# LEDS.net
KiCad netlist of a schematic drawn in Altium Designer
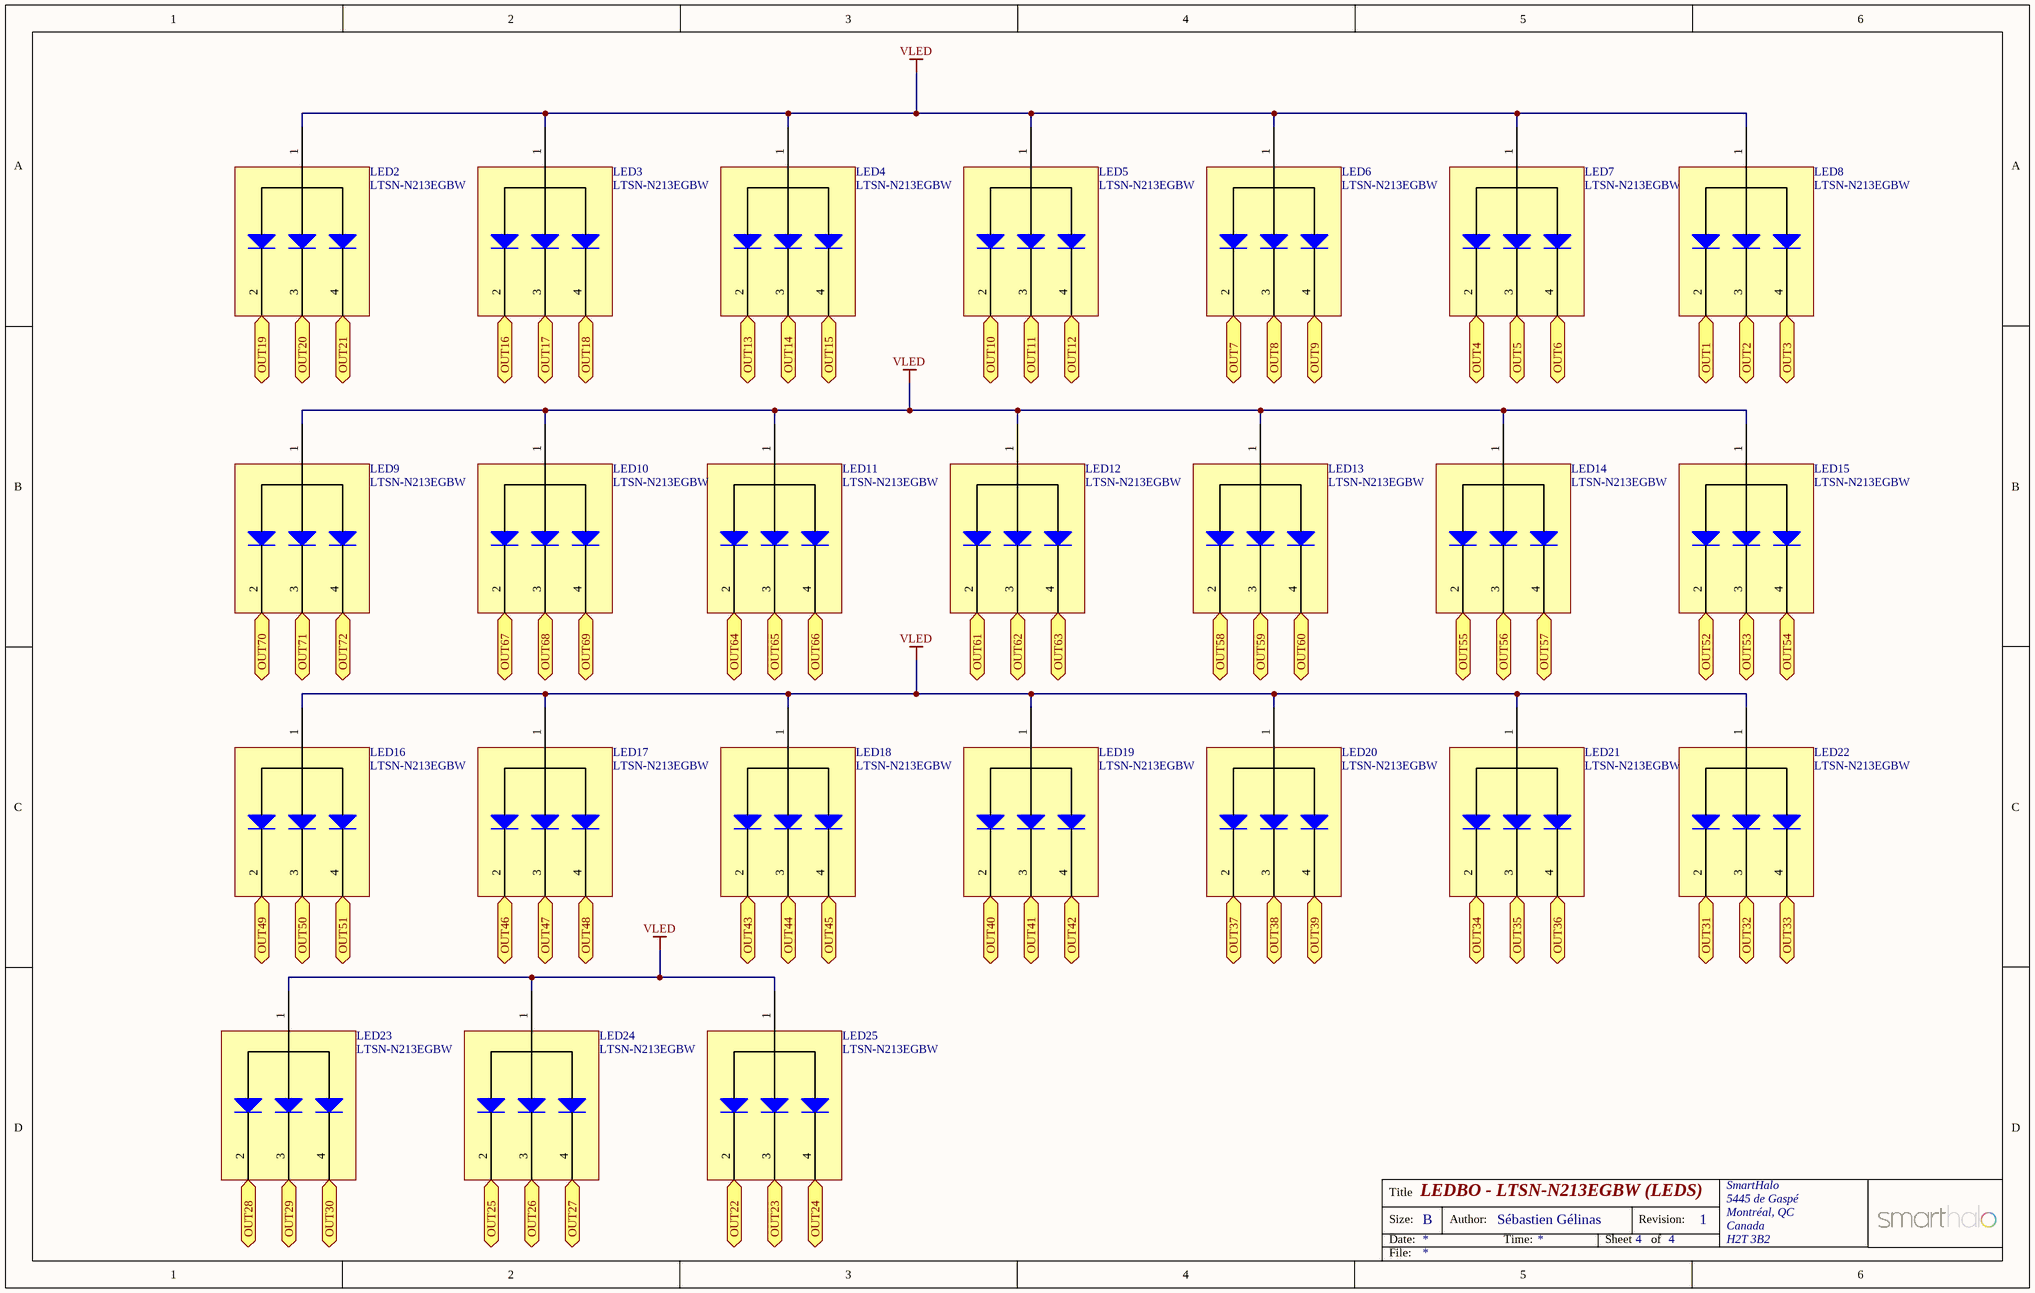
[diagram p0: LEDS.SchDoc]

(export (version "E")
  (design (tool "Eeschema 10.0.6"))
  (components
    (comp (ref "LED2")
      (value "LTSN-N213EGBW")
      (footprint "LTSN-N213EGBW")
      (description "LED SMD LTSN-N213EGBW")
      (fields (field (name "MANUFACTURER") "LiteOn"))
      (libsource (lib "SmartHalo") (part "LTSN-N213EGBW"))
    )
    (comp (ref "LED3")
      (value "LTSN-N213EGBW")
      (footprint "LTSN-N213EGBW")
      (description "LED SMD LTSN-N213EGBW")
      (fields (field (name "MANUFACTURER") "LiteOn"))
      (libsource (lib "SmartHalo") (part "LTSN-N213EGBW"))
    )
    (comp (ref "LED4")
      (value "LTSN-N213EGBW")
      (footprint "LTSN-N213EGBW")
      (description "LED SMD LTSN-N213EGBW")
      (fields (field (name "MANUFACTURER") "LiteOn"))
      (libsource (lib "SmartHalo") (part "LTSN-N213EGBW"))
    )
    (comp (ref "LED5")
      (value "LTSN-N213EGBW")
      (footprint "LTSN-N213EGBW")
      (description "LED SMD LTSN-N213EGBW")
      (fields (field (name "MANUFACTURER") "LiteOn"))
      (libsource (lib "SmartHalo") (part "LTSN-N213EGBW"))
    )
    (comp (ref "LED6")
      (value "LTSN-N213EGBW")
      (footprint "LTSN-N213EGBW")
      (description "LED SMD LTSN-N213EGBW")
      (fields (field (name "MANUFACTURER") "LiteOn"))
      (libsource (lib "SmartHalo") (part "LTSN-N213EGBW"))
    )
    (comp (ref "LED7")
      (value "LTSN-N213EGBW")
      (footprint "LTSN-N213EGBW")
      (description "LED SMD LTSN-N213EGBW")
      (fields (field (name "MANUFACTURER") "LiteOn"))
      (libsource (lib "SmartHalo") (part "LTSN-N213EGBW"))
    )
    (comp (ref "LED8")
      (value "LTSN-N213EGBW")
      (footprint "LTSN-N213EGBW")
      (description "LED SMD LTSN-N213EGBW")
      (fields (field (name "MANUFACTURER") "LiteOn"))
      (libsource (lib "SmartHalo") (part "LTSN-N213EGBW"))
    )
    (comp (ref "LED9")
      (value "LTSN-N213EGBW")
      (footprint "LTSN-N213EGBW")
      (description "LED SMD LTSN-N213EGBW")
      (fields (field (name "MANUFACTURER") "LiteOn"))
      (libsource (lib "SmartHalo") (part "LTSN-N213EGBW"))
    )
    (comp (ref "LED10")
      (value "LTSN-N213EGBW")
      (footprint "LTSN-N213EGBW")
      (description "LED SMD LTSN-N213EGBW")
      (fields (field (name "MANUFACTURER") "LiteOn"))
      (libsource (lib "SmartHalo") (part "LTSN-N213EGBW"))
    )
    (comp (ref "LED11")
      (value "LTSN-N213EGBW")
      (footprint "LTSN-N213EGBW")
      (description "LED SMD LTSN-N213EGBW")
      (fields (field (name "MANUFACTURER") "LiteOn"))
      (libsource (lib "SmartHalo") (part "LTSN-N213EGBW"))
    )
    (comp (ref "LED12")
      (value "LTSN-N213EGBW")
      (footprint "LTSN-N213EGBW")
      (description "LED SMD LTSN-N213EGBW")
      (fields (field (name "MANUFACTURER") "LiteOn"))
      (libsource (lib "SmartHalo") (part "LTSN-N213EGBW"))
    )
    (comp (ref "LED13")
      (value "LTSN-N213EGBW")
      (footprint "LTSN-N213EGBW")
      (description "LED SMD LTSN-N213EGBW")
      (fields (field (name "MANUFACTURER") "LiteOn"))
      (libsource (lib "SmartHalo") (part "LTSN-N213EGBW"))
    )
    (comp (ref "LED14")
      (value "LTSN-N213EGBW")
      (footprint "LTSN-N213EGBW")
      (description "LED SMD LTSN-N213EGBW")
      (fields (field (name "MANUFACTURER") "LiteOn"))
      (libsource (lib "SmartHalo") (part "LTSN-N213EGBW"))
    )
    (comp (ref "LED15")
      (value "LTSN-N213EGBW")
      (footprint "LTSN-N213EGBW")
      (description "LED SMD LTSN-N213EGBW")
      (fields (field (name "MANUFACTURER") "LiteOn"))
      (libsource (lib "SmartHalo") (part "LTSN-N213EGBW"))
    )
    (comp (ref "LED16")
      (value "LTSN-N213EGBW")
      (footprint "LTSN-N213EGBW")
      (description "LED SMD LTSN-N213EGBW")
      (fields (field (name "MANUFACTURER") "LiteOn"))
      (libsource (lib "SmartHalo") (part "LTSN-N213EGBW"))
    )
    (comp (ref "LED17")
      (value "LTSN-N213EGBW")
      (footprint "LTSN-N213EGBW")
      (description "LED SMD LTSN-N213EGBW")
      (fields (field (name "MANUFACTURER") "LiteOn"))
      (libsource (lib "SmartHalo") (part "LTSN-N213EGBW"))
    )
    (comp (ref "LED18")
      (value "LTSN-N213EGBW")
      (footprint "LTSN-N213EGBW")
      (description "LED SMD LTSN-N213EGBW")
      (fields (field (name "MANUFACTURER") "LiteOn"))
      (libsource (lib "SmartHalo") (part "LTSN-N213EGBW"))
    )
    (comp (ref "LED19")
      (value "LTSN-N213EGBW")
      (footprint "LTSN-N213EGBW")
      (description "LED SMD LTSN-N213EGBW")
      (fields (field (name "MANUFACTURER") "LiteOn"))
      (libsource (lib "SmartHalo") (part "LTSN-N213EGBW"))
    )
    (comp (ref "LED20")
      (value "LTSN-N213EGBW")
      (footprint "LTSN-N213EGBW")
      (description "LED SMD LTSN-N213EGBW")
      (fields (field (name "MANUFACTURER") "LiteOn"))
      (libsource (lib "SmartHalo") (part "LTSN-N213EGBW"))
    )
    (comp (ref "LED21")
      (value "LTSN-N213EGBW")
      (footprint "LTSN-N213EGBW")
      (description "LED SMD LTSN-N213EGBW")
      (fields (field (name "MANUFACTURER") "LiteOn"))
      (libsource (lib "SmartHalo") (part "LTSN-N213EGBW"))
    )
    (comp (ref "LED22")
      (value "LTSN-N213EGBW")
      (footprint "LTSN-N213EGBW")
      (description "LED SMD LTSN-N213EGBW")
      (fields (field (name "MANUFACTURER") "LiteOn"))
      (libsource (lib "SmartHalo") (part "LTSN-N213EGBW"))
    )
    (comp (ref "LED23")
      (value "LTSN-N213EGBW")
      (footprint "LTSN-N213EGBW")
      (description "LED SMD LTSN-N213EGBW")
      (fields (field (name "MANUFACTURER") "LiteOn"))
      (libsource (lib "SmartHalo") (part "LTSN-N213EGBW"))
    )
    (comp (ref "LED24")
      (value "LTSN-N213EGBW")
      (footprint "LTSN-N213EGBW")
      (description "LED SMD LTSN-N213EGBW")
      (fields (field (name "MANUFACTURER") "LiteOn"))
      (libsource (lib "SmartHalo") (part "LTSN-N213EGBW"))
    )
    (comp (ref "LED25")
      (value "LTSN-N213EGBW")
      (footprint "LTSN-N213EGBW")
      (description "LED SMD LTSN-N213EGBW")
      (fields (field (name "MANUFACTURER") "LiteOn"))
      (libsource (lib "SmartHalo") (part "LTSN-N213EGBW"))
    )
  )
  (nets
    (net (code "1") (name "/OUT1") (class "Default")
      (node (ref "LED8") (pin "2") (pinfunction "Cathode_Red_2") (pintype "passive"))
    )
    (net (code "2") (name "/OUT2") (class "Default")
      (node (ref "LED8") (pin "3") (pinfunction "Cathode_Green_3") (pintype "passive"))
    )
    (net (code "3") (name "/OUT3") (class "Default")
      (node (ref "LED8") (pin "4") (pinfunction "Cathode_Blue_4") (pintype "passive"))
    )
    (net (code "4") (name "/OUT4") (class "Default")
      (node (ref "LED7") (pin "2") (pinfunction "Cathode_Red_2") (pintype "passive"))
    )
    (net (code "5") (name "/OUT5") (class "Default")
      (node (ref "LED7") (pin "3") (pinfunction "Cathode_Green_3") (pintype "passive"))
    )
    (net (code "6") (name "/OUT6") (class "Default")
      (node (ref "LED7") (pin "4") (pinfunction "Cathode_Blue_4") (pintype "passive"))
    )
    (net (code "7") (name "/OUT7") (class "Default")
      (node (ref "LED6") (pin "2") (pinfunction "Cathode_Red_2") (pintype "passive"))
    )
    (net (code "8") (name "/OUT8") (class "Default")
      (node (ref "LED6") (pin "3") (pinfunction "Cathode_Green_3") (pintype "passive"))
    )
    (net (code "9") (name "/OUT9") (class "Default")
      (node (ref "LED6") (pin "4") (pinfunction "Cathode_Blue_4") (pintype "passive"))
    )
    (net (code "10") (name "/OUT10") (class "Default")
      (node (ref "LED5") (pin "2") (pinfunction "Cathode_Red_2") (pintype "passive"))
    )
    (net (code "11") (name "/OUT11") (class "Default")
      (node (ref "LED5") (pin "3") (pinfunction "Cathode_Green_3") (pintype "passive"))
    )
    (net (code "12") (name "/OUT12") (class "Default")
      (node (ref "LED5") (pin "4") (pinfunction "Cathode_Blue_4") (pintype "passive"))
    )
    (net (code "13") (name "/OUT13") (class "Default")
      (node (ref "LED4") (pin "2") (pinfunction "Cathode_Red_2") (pintype "passive"))
    )
    (net (code "14") (name "/OUT14") (class "Default")
      (node (ref "LED4") (pin "3") (pinfunction "Cathode_Green_3") (pintype "passive"))
    )
    (net (code "15") (name "/OUT15") (class "Default")
      (node (ref "LED4") (pin "4") (pinfunction "Cathode_Blue_4") (pintype "passive"))
    )
    (net (code "16") (name "/OUT16") (class "Default")
      (node (ref "LED3") (pin "2") (pinfunction "Cathode_Red_2") (pintype "passive"))
    )
    (net (code "17") (name "/OUT17") (class "Default")
      (node (ref "LED3") (pin "3") (pinfunction "Cathode_Green_3") (pintype "passive"))
    )
    (net (code "18") (name "/OUT18") (class "Default")
      (node (ref "LED3") (pin "4") (pinfunction "Cathode_Blue_4") (pintype "passive"))
    )
    (net (code "19") (name "/OUT19") (class "Default")
      (node (ref "LED2") (pin "2") (pinfunction "Cathode_Red_2") (pintype "passive"))
    )
    (net (code "20") (name "/OUT20") (class "Default")
      (node (ref "LED2") (pin "3") (pinfunction "Cathode_Green_3") (pintype "passive"))
    )
    (net (code "21") (name "/OUT21") (class "Default")
      (node (ref "LED2") (pin "4") (pinfunction "Cathode_Blue_4") (pintype "passive"))
    )
    (net (code "22") (name "/OUT22") (class "Default")
      (node (ref "LED25") (pin "2") (pinfunction "Cathode_Red_2") (pintype "passive"))
    )
    (net (code "23") (name "/OUT23") (class "Default")
      (node (ref "LED25") (pin "3") (pinfunction "Cathode_Green_3") (pintype "passive"))
    )
    (net (code "24") (name "/OUT24") (class "Default")
      (node (ref "LED25") (pin "4") (pinfunction "Cathode_Blue_4") (pintype "passive"))
    )
    (net (code "25") (name "/OUT25") (class "Default")
      (node (ref "LED24") (pin "2") (pinfunction "Cathode_Red_2") (pintype "passive"))
    )
    (net (code "26") (name "/OUT26") (class "Default")
      (node (ref "LED24") (pin "3") (pinfunction "Cathode_Green_3") (pintype "passive"))
    )
    (net (code "27") (name "/OUT27") (class "Default")
      (node (ref "LED24") (pin "4") (pinfunction "Cathode_Blue_4") (pintype "passive"))
    )
    (net (code "28") (name "/OUT28") (class "Default")
      (node (ref "LED23") (pin "2") (pinfunction "Cathode_Red_2") (pintype "passive"))
    )
    (net (code "29") (name "/OUT29") (class "Default")
      (node (ref "LED23") (pin "3") (pinfunction "Cathode_Green_3") (pintype "passive"))
    )
    (net (code "30") (name "/OUT30") (class "Default")
      (node (ref "LED23") (pin "4") (pinfunction "Cathode_Blue_4") (pintype "passive"))
    )
    (net (code "31") (name "/OUT31") (class "Default")
      (node (ref "LED22") (pin "2") (pinfunction "Cathode_Red_2") (pintype "passive"))
    )
    (net (code "32") (name "/OUT32") (class "Default")
      (node (ref "LED22") (pin "3") (pinfunction "Cathode_Green_3") (pintype "passive"))
    )
    (net (code "33") (name "/OUT33") (class "Default")
      (node (ref "LED22") (pin "4") (pinfunction "Cathode_Blue_4") (pintype "passive"))
    )
    (net (code "34") (name "/OUT34") (class "Default")
      (node (ref "LED21") (pin "2") (pinfunction "Cathode_Red_2") (pintype "passive"))
    )
    (net (code "35") (name "/OUT35") (class "Default")
      (node (ref "LED21") (pin "3") (pinfunction "Cathode_Green_3") (pintype "passive"))
    )
    (net (code "36") (name "/OUT36") (class "Default")
      (node (ref "LED21") (pin "4") (pinfunction "Cathode_Blue_4") (pintype "passive"))
    )
    (net (code "37") (name "/OUT37") (class "Default")
      (node (ref "LED20") (pin "2") (pinfunction "Cathode_Red_2") (pintype "passive"))
    )
    (net (code "38") (name "/OUT38") (class "Default")
      (node (ref "LED20") (pin "3") (pinfunction "Cathode_Green_3") (pintype "passive"))
    )
    (net (code "39") (name "/OUT39") (class "Default")
      (node (ref "LED20") (pin "4") (pinfunction "Cathode_Blue_4") (pintype "passive"))
    )
    (net (code "40") (name "/OUT40") (class "Default")
      (node (ref "LED19") (pin "2") (pinfunction "Cathode_Red_2") (pintype "passive"))
    )
    (net (code "41") (name "/OUT41") (class "Default")
      (node (ref "LED19") (pin "3") (pinfunction "Cathode_Green_3") (pintype "passive"))
    )
    (net (code "42") (name "/OUT42") (class "Default")
      (node (ref "LED19") (pin "4") (pinfunction "Cathode_Blue_4") (pintype "passive"))
    )
    (net (code "43") (name "/OUT43") (class "Default")
      (node (ref "LED18") (pin "2") (pinfunction "Cathode_Red_2") (pintype "passive"))
    )
    (net (code "44") (name "/OUT44") (class "Default")
      (node (ref "LED18") (pin "3") (pinfunction "Cathode_Green_3") (pintype "passive"))
    )
    (net (code "45") (name "/OUT45") (class "Default")
      (node (ref "LED18") (pin "4") (pinfunction "Cathode_Blue_4") (pintype "passive"))
    )
    (net (code "46") (name "/OUT46") (class "Default")
      (node (ref "LED17") (pin "2") (pinfunction "Cathode_Red_2") (pintype "passive"))
    )
    (net (code "47") (name "/OUT47") (class "Default")
      (node (ref "LED17") (pin "3") (pinfunction "Cathode_Green_3") (pintype "passive"))
    )
    (net (code "48") (name "/OUT48") (class "Default")
      (node (ref "LED17") (pin "4") (pinfunction "Cathode_Blue_4") (pintype "passive"))
    )
    (net (code "49") (name "/OUT49") (class "Default")
      (node (ref "LED16") (pin "2") (pinfunction "Cathode_Red_2") (pintype "passive"))
    )
    (net (code "50") (name "/OUT50") (class "Default")
      (node (ref "LED16") (pin "3") (pinfunction "Cathode_Green_3") (pintype "passive"))
    )
    (net (code "51") (name "/OUT51") (class "Default")
      (node (ref "LED16") (pin "4") (pinfunction "Cathode_Blue_4") (pintype "passive"))
    )
    (net (code "52") (name "/OUT52") (class "Default")
      (node (ref "LED15") (pin "2") (pinfunction "Cathode_Red_2") (pintype "passive"))
    )
    (net (code "53") (name "/OUT53") (class "Default")
      (node (ref "LED15") (pin "3") (pinfunction "Cathode_Green_3") (pintype "passive"))
    )
    (net (code "54") (name "/OUT54") (class "Default")
      (node (ref "LED15") (pin "4") (pinfunction "Cathode_Blue_4") (pintype "passive"))
    )
    (net (code "55") (name "/OUT55") (class "Default")
      (node (ref "LED14") (pin "2") (pinfunction "Cathode_Red_2") (pintype "passive"))
    )
    (net (code "56") (name "/OUT56") (class "Default")
      (node (ref "LED14") (pin "3") (pinfunction "Cathode_Green_3") (pintype "passive"))
    )
    (net (code "57") (name "/OUT57") (class "Default")
      (node (ref "LED14") (pin "4") (pinfunction "Cathode_Blue_4") (pintype "passive"))
    )
    (net (code "58") (name "/OUT58") (class "Default")
      (node (ref "LED13") (pin "2") (pinfunction "Cathode_Red_2") (pintype "passive"))
    )
    (net (code "59") (name "/OUT59") (class "Default")
      (node (ref "LED13") (pin "3") (pinfunction "Cathode_Green_3") (pintype "passive"))
    )
    (net (code "60") (name "/OUT60") (class "Default")
      (node (ref "LED13") (pin "4") (pinfunction "Cathode_Blue_4") (pintype "passive"))
    )
    (net (code "61") (name "/OUT61") (class "Default")
      (node (ref "LED12") (pin "2") (pinfunction "Cathode_Red_2") (pintype "passive"))
    )
    (net (code "62") (name "/OUT62") (class "Default")
      (node (ref "LED12") (pin "3") (pinfunction "Cathode_Green_3") (pintype "passive"))
    )
    (net (code "63") (name "/OUT63") (class "Default")
      (node (ref "LED12") (pin "4") (pinfunction "Cathode_Blue_4") (pintype "passive"))
    )
    (net (code "64") (name "/OUT64") (class "Default")
      (node (ref "LED11") (pin "2") (pinfunction "Cathode_Red_2") (pintype "passive"))
    )
    (net (code "65") (name "/OUT65") (class "Default")
      (node (ref "LED11") (pin "3") (pinfunction "Cathode_Green_3") (pintype "passive"))
    )
    (net (code "66") (name "/OUT66") (class "Default")
      (node (ref "LED11") (pin "4") (pinfunction "Cathode_Blue_4") (pintype "passive"))
    )
    (net (code "67") (name "/OUT67") (class "Default")
      (node (ref "LED10") (pin "2") (pinfunction "Cathode_Red_2") (pintype "passive"))
    )
    (net (code "68") (name "/OUT68") (class "Default")
      (node (ref "LED10") (pin "3") (pinfunction "Cathode_Green_3") (pintype "passive"))
    )
    (net (code "69") (name "/OUT69") (class "Default")
      (node (ref "LED10") (pin "4") (pinfunction "Cathode_Blue_4") (pintype "passive"))
    )
    (net (code "70") (name "/OUT70") (class "Default")
      (node (ref "LED9") (pin "2") (pinfunction "Cathode_Red_2") (pintype "passive"))
    )
    (net (code "71") (name "/OUT71") (class "Default")
      (node (ref "LED9") (pin "3") (pinfunction "Cathode_Green_3") (pintype "passive"))
    )
    (net (code "72") (name "/OUT72") (class "Default")
      (node (ref "LED9") (pin "4") (pinfunction "Cathode_Blue_4") (pintype "passive"))
    )
    (net (code "73") (name "VLED") (class "Default")
      (node (ref "LED10") (pin "1") (pinfunction "Anode_1") (pintype "passive"))
      (node (ref "LED11") (pin "1") (pinfunction "Anode_1") (pintype "passive"))
      (node (ref "LED12") (pin "1") (pinfunction "Anode_1") (pintype "passive"))
      (node (ref "LED13") (pin "1") (pinfunction "Anode_1") (pintype "passive"))
      (node (ref "LED14") (pin "1") (pinfunction "Anode_1") (pintype "passive"))
      (node (ref "LED15") (pin "1") (pinfunction "Anode_1") (pintype "passive"))
      (node (ref "LED16") (pin "1") (pinfunction "Anode_1") (pintype "passive"))
      (node (ref "LED17") (pin "1") (pinfunction "Anode_1") (pintype "passive"))
      (node (ref "LED18") (pin "1") (pinfunction "Anode_1") (pintype "passive"))
      (node (ref "LED19") (pin "1") (pinfunction "Anode_1") (pintype "passive"))
      (node (ref "LED2") (pin "1") (pinfunction "Anode_1") (pintype "passive"))
      (node (ref "LED20") (pin "1") (pinfunction "Anode_1") (pintype "passive"))
      (node (ref "LED21") (pin "1") (pinfunction "Anode_1") (pintype "passive"))
      (node (ref "LED22") (pin "1") (pinfunction "Anode_1") (pintype "passive"))
      (node (ref "LED23") (pin "1") (pinfunction "Anode_1") (pintype "passive"))
      (node (ref "LED24") (pin "1") (pinfunction "Anode_1") (pintype "passive"))
      (node (ref "LED25") (pin "1") (pinfunction "Anode_1") (pintype "passive"))
      (node (ref "LED3") (pin "1") (pinfunction "Anode_1") (pintype "passive"))
      (node (ref "LED4") (pin "1") (pinfunction "Anode_1") (pintype "passive"))
      (node (ref "LED5") (pin "1") (pinfunction "Anode_1") (pintype "passive"))
      (node (ref "LED6") (pin "1") (pinfunction "Anode_1") (pintype "passive"))
      (node (ref "LED7") (pin "1") (pinfunction "Anode_1") (pintype "passive"))
      (node (ref "LED8") (pin "1") (pinfunction "Anode_1") (pintype "passive"))
      (node (ref "LED9") (pin "1") (pinfunction "Anode_1") (pintype "passive"))
    )
  )
)
